# MCP23017_I_v1_0.net
KiCad netlist of a schematic drawn in EAGLE
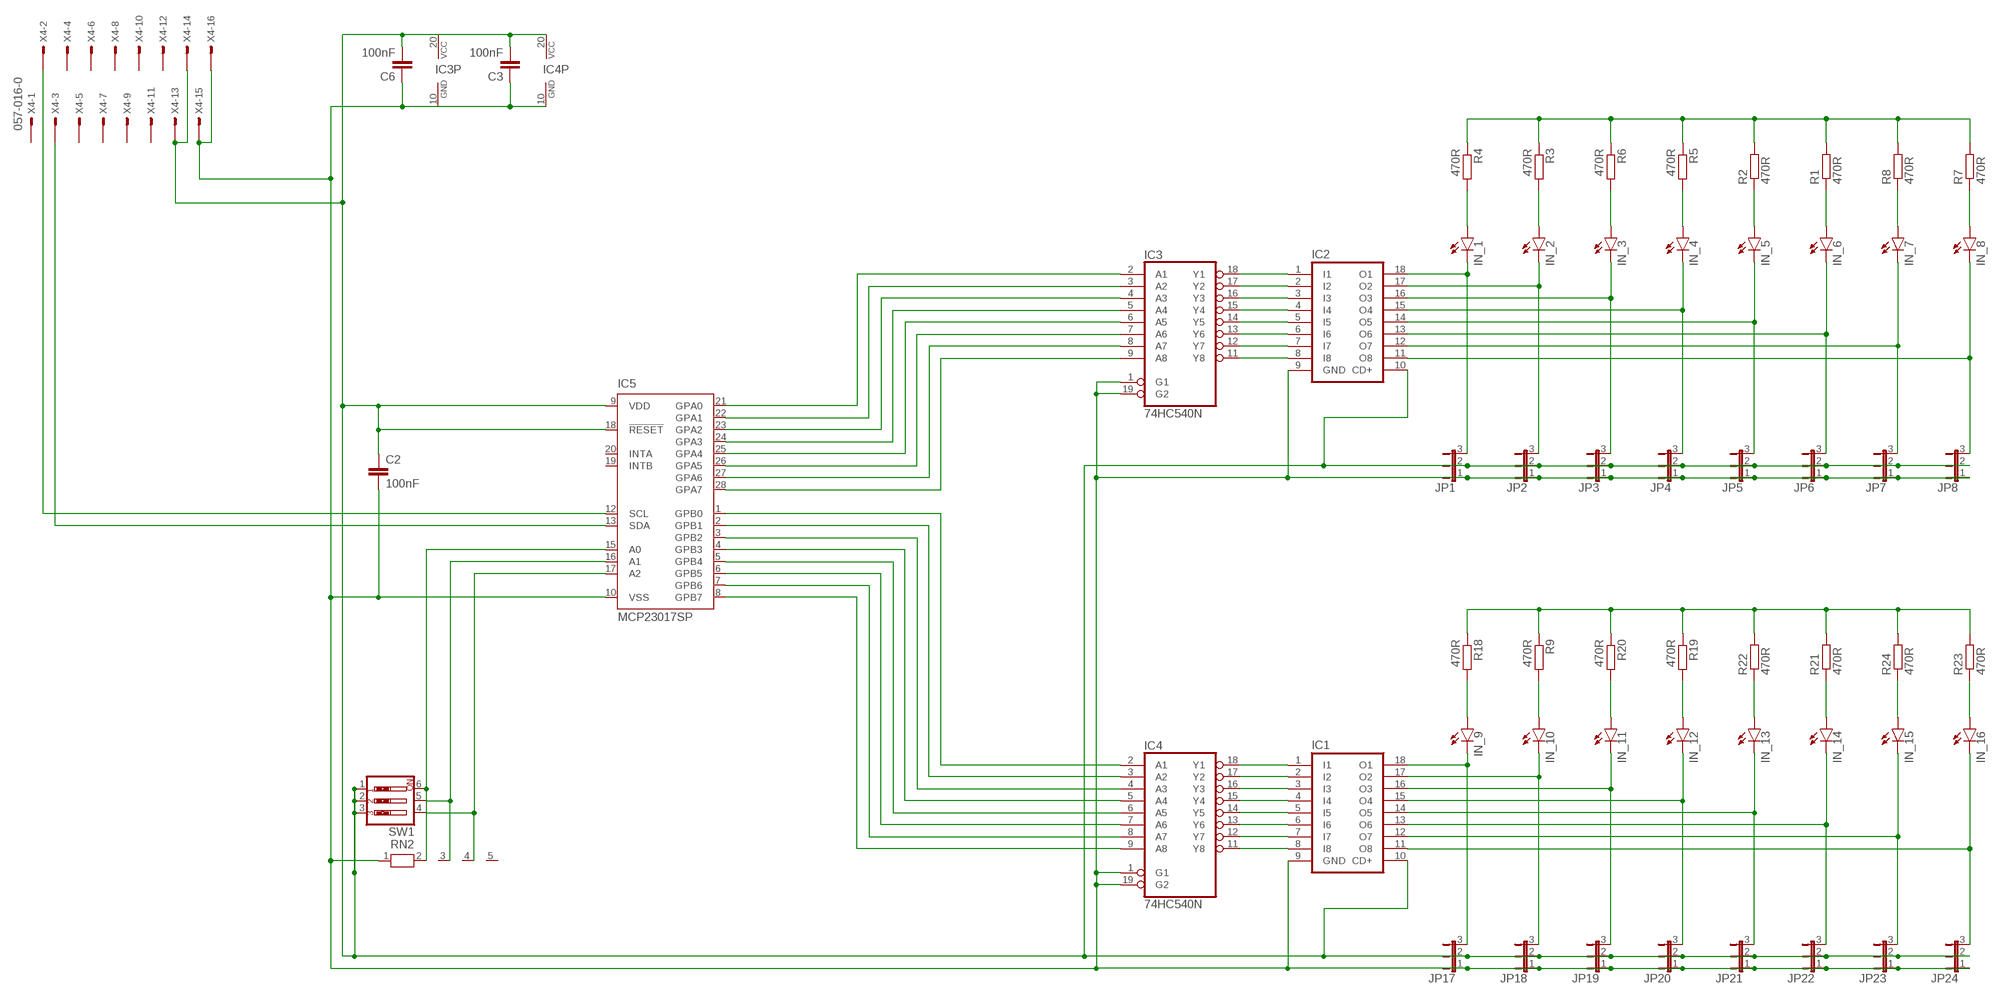
[diagram p0: schematic, sheet 1]

(export (version "E")
  (design (tool "Eeschema 10.0.6"))
  (components
    (comp (ref "C2")
      (value "100nF")
      (footprint "eagle-import:C025-024X044")
      (libsource (lib "eagle-import") (part "C-EU025-024X044"))
    )
    (comp (ref "C3")
      (value "100nF")
      (footprint "eagle-import:C025-024X044")
      (libsource (lib "eagle-import") (part "C-EU025-024X044"))
    )
    (comp (ref "C6")
      (value "100nF")
      (footprint "eagle-import:C025-024X044")
      (libsource (lib "eagle-import") (part "C-EU025-024X044"))
    )
    (comp (ref "IC1")
      (value "ULN2803A")
      (footprint "eagle-import:DIL18")
      (libsource (lib "eagle-import") (part "ULN2803A"))
    )
    (comp (ref "IC2")
      (value "ULN2803A")
      (footprint "eagle-import:DIL18")
      (libsource (lib "eagle-import") (part "ULN2803A"))
    )
    (comp (ref "IC3")
      (value "74HC540N")
      (footprint "eagle-import:DIL20")
      (libsource (lib "eagle-import") (part "74540NHC"))
    )
    (comp (ref "IC4")
      (value "74HC540N")
      (footprint "eagle-import:DIL20")
      (libsource (lib "eagle-import") (part "74540NHC"))
    )
    (comp (ref "IC5")
      (value "MCP23017SP")
      (footprint "eagle-import:DIL28-3")
      (libsource (lib "eagle-import") (part "MCP23017SP"))
    )
    (comp (ref "IN_1")
      (value "LED3MM")
      (footprint "eagle-import:LED3MM")
      (libsource (lib "eagle-import") (part "LED3MM"))
    )
    (comp (ref "IN_2")
      (value "LED3MM")
      (footprint "eagle-import:LED3MM")
      (libsource (lib "eagle-import") (part "LED3MM"))
    )
    (comp (ref "IN_3")
      (value "LED3MM")
      (footprint "eagle-import:LED3MM")
      (libsource (lib "eagle-import") (part "LED3MM"))
    )
    (comp (ref "IN_4")
      (value "LED3MM")
      (footprint "eagle-import:LED3MM")
      (libsource (lib "eagle-import") (part "LED3MM"))
    )
    (comp (ref "IN_5")
      (value "LED3MM")
      (footprint "eagle-import:LED3MM")
      (libsource (lib "eagle-import") (part "LED3MM"))
    )
    (comp (ref "IN_6")
      (value "LED3MM")
      (footprint "eagle-import:LED3MM")
      (libsource (lib "eagle-import") (part "LED3MM"))
    )
    (comp (ref "IN_7")
      (value "LED3MM")
      (footprint "eagle-import:LED3MM")
      (libsource (lib "eagle-import") (part "LED3MM"))
    )
    (comp (ref "IN_8")
      (value "LED3MM")
      (footprint "eagle-import:LED3MM")
      (libsource (lib "eagle-import") (part "LED3MM"))
    )
    (comp (ref "IN_9")
      (value "LED3MM")
      (footprint "eagle-import:LED3MM")
      (libsource (lib "eagle-import") (part "LED3MM"))
    )
    (comp (ref "IN_10")
      (value "LED3MM")
      (footprint "eagle-import:LED3MM")
      (libsource (lib "eagle-import") (part "LED3MM"))
    )
    (comp (ref "IN_11")
      (value "LED3MM")
      (footprint "eagle-import:LED3MM")
      (libsource (lib "eagle-import") (part "LED3MM"))
    )
    (comp (ref "IN_12")
      (value "LED3MM")
      (footprint "eagle-import:LED3MM")
      (libsource (lib "eagle-import") (part "LED3MM"))
    )
    (comp (ref "IN_13")
      (value "LED3MM")
      (footprint "eagle-import:LED3MM")
      (libsource (lib "eagle-import") (part "LED3MM"))
    )
    (comp (ref "IN_14")
      (value "LED3MM")
      (footprint "eagle-import:LED3MM")
      (libsource (lib "eagle-import") (part "LED3MM"))
    )
    (comp (ref "IN_15")
      (value "LED3MM")
      (footprint "eagle-import:LED3MM")
      (libsource (lib "eagle-import") (part "LED3MM"))
    )
    (comp (ref "IN_16")
      (value "LED3MM")
      (footprint "eagle-import:LED3MM")
      (libsource (lib "eagle-import") (part "LED3MM"))
    )
    (comp (ref "JP1")
      (value "JP2E")
      (footprint "eagle-import:JP2")
      (libsource (lib "eagle-import") (part "JP2E"))
    )
    (comp (ref "JP2")
      (value "JP2E")
      (footprint "eagle-import:JP2")
      (libsource (lib "eagle-import") (part "JP2E"))
    )
    (comp (ref "JP3")
      (value "JP2E")
      (footprint "eagle-import:JP2")
      (libsource (lib "eagle-import") (part "JP2E"))
    )
    (comp (ref "JP4")
      (value "JP2E")
      (footprint "eagle-import:JP2")
      (libsource (lib "eagle-import") (part "JP2E"))
    )
    (comp (ref "JP5")
      (value "JP2E")
      (footprint "eagle-import:JP2")
      (libsource (lib "eagle-import") (part "JP2E"))
    )
    (comp (ref "JP6")
      (value "JP2E")
      (footprint "eagle-import:JP2")
      (libsource (lib "eagle-import") (part "JP2E"))
    )
    (comp (ref "JP7")
      (value "JP2E")
      (footprint "eagle-import:JP2")
      (libsource (lib "eagle-import") (part "JP2E"))
    )
    (comp (ref "JP8")
      (value "JP2E")
      (footprint "eagle-import:JP2")
      (libsource (lib "eagle-import") (part "JP2E"))
    )
    (comp (ref "JP17")
      (value "JP2E")
      (footprint "eagle-import:JP2")
      (libsource (lib "eagle-import") (part "JP2E"))
    )
    (comp (ref "JP18")
      (value "JP2E")
      (footprint "eagle-import:JP2")
      (libsource (lib "eagle-import") (part "JP2E"))
    )
    (comp (ref "JP19")
      (value "JP2E")
      (footprint "eagle-import:JP2")
      (libsource (lib "eagle-import") (part "JP2E"))
    )
    (comp (ref "JP20")
      (value "JP2E")
      (footprint "eagle-import:JP2")
      (libsource (lib "eagle-import") (part "JP2E"))
    )
    (comp (ref "JP21")
      (value "JP2E")
      (footprint "eagle-import:JP2")
      (libsource (lib "eagle-import") (part "JP2E"))
    )
    (comp (ref "JP22")
      (value "JP2E")
      (footprint "eagle-import:JP2")
      (libsource (lib "eagle-import") (part "JP2E"))
    )
    (comp (ref "JP23")
      (value "JP2E")
      (footprint "eagle-import:JP2")
      (libsource (lib "eagle-import") (part "JP2E"))
    )
    (comp (ref "JP24")
      (value "JP2E")
      (footprint "eagle-import:JP2")
      (libsource (lib "eagle-import") (part "JP2E"))
    )
    (comp (ref "R1")
      (value "470R")
      (footprint "eagle-import:0309_10")
      (libsource (lib "eagle-import") (part "R-EU_0309/10"))
    )
    (comp (ref "R2")
      (value "470R")
      (footprint "eagle-import:0309_10")
      (libsource (lib "eagle-import") (part "R-EU_0309/10"))
    )
    (comp (ref "R3")
      (value "470R")
      (footprint "eagle-import:0309_10")
      (libsource (lib "eagle-import") (part "R-EU_0309/10"))
    )
    (comp (ref "R4")
      (value "470R")
      (footprint "eagle-import:0309_10")
      (libsource (lib "eagle-import") (part "R-EU_0309/10"))
    )
    (comp (ref "R5")
      (value "470R")
      (footprint "eagle-import:0309_10")
      (libsource (lib "eagle-import") (part "R-EU_0309/10"))
    )
    (comp (ref "R6")
      (value "470R")
      (footprint "eagle-import:0309_10")
      (libsource (lib "eagle-import") (part "R-EU_0309/10"))
    )
    (comp (ref "R7")
      (value "470R")
      (footprint "eagle-import:0309_10")
      (libsource (lib "eagle-import") (part "R-EU_0309/10"))
    )
    (comp (ref "R8")
      (value "470R")
      (footprint "eagle-import:0309_10")
      (libsource (lib "eagle-import") (part "R-EU_0309/10"))
    )
    (comp (ref "R9")
      (value "470R")
      (footprint "eagle-import:0309_10")
      (libsource (lib "eagle-import") (part "R-EU_0309/10"))
    )
    (comp (ref "R18")
      (value "470R")
      (footprint "eagle-import:0309_10")
      (libsource (lib "eagle-import") (part "R-EU_0309/10"))
    )
    (comp (ref "R19")
      (value "470R")
      (footprint "eagle-import:0309_10")
      (libsource (lib "eagle-import") (part "R-EU_0309/10"))
    )
    (comp (ref "R20")
      (value "470R")
      (footprint "eagle-import:0309_10")
      (libsource (lib "eagle-import") (part "R-EU_0309/10"))
    )
    (comp (ref "R21")
      (value "470R")
      (footprint "eagle-import:0309_10")
      (libsource (lib "eagle-import") (part "R-EU_0309/10"))
    )
    (comp (ref "R22")
      (value "470R")
      (footprint "eagle-import:0309_10")
      (libsource (lib "eagle-import") (part "R-EU_0309/10"))
    )
    (comp (ref "R23")
      (value "470R")
      (footprint "eagle-import:0309_10")
      (libsource (lib "eagle-import") (part "R-EU_0309/10"))
    )
    (comp (ref "R24")
      (value "470R")
      (footprint "eagle-import:0309_10")
      (libsource (lib "eagle-import") (part "R-EU_0309/10"))
    )
    (comp (ref "RN2")
      (value "RN04")
      (footprint "eagle-import:RN-5")
      (libsource (lib "eagle-import") (part "RN04"))
    )
    (comp (ref "SW1")
      (value "SW_DIP-3")
      (footprint "eagle-import:EDG-03")
      (libsource (lib "eagle-import") (part "SW_DIP-3"))
    )
    (comp (ref "X4")
      (value "057-016-0")
      (footprint "eagle-import:057-016-0")
      (libsource (lib "eagle-import") (part "057-016-0"))
    )
  )
  (nets
    (net (code "1") (name "/VCC5.2") (class "Default")
      (node (ref "C2") (pin "1") (pinfunction "1_1") (pintype "passive"))
      (node (ref "C3") (pin "2") (pinfunction "2_2") (pintype "passive"))
      (node (ref "C6") (pin "2") (pinfunction "2_2") (pintype "passive"))
      (node (ref "IC1") (pin "10") (pinfunction "CD+_10") (pintype "passive"))
      (node (ref "IC2") (pin "10") (pinfunction "CD+_10") (pintype "passive"))
      (node (ref "IC3") (pin "20") (pinfunction "VCC_20") (pintype "power_in"))
      (node (ref "IC4") (pin "20") (pinfunction "VCC_20") (pintype "power_in"))
      (node (ref "IC5") (pin "18") (pinfunction "~{RESET}_18") (pintype "input"))
      (node (ref "IC5") (pin "9") (pinfunction "VDD_9") (pintype "power_in"))
      (node (ref "JP1") (pin "2") (pinfunction "2_2") (pintype "passive"))
      (node (ref "JP17") (pin "2") (pinfunction "2_2") (pintype "passive"))
      (node (ref "JP18") (pin "2") (pinfunction "2_2") (pintype "passive"))
      (node (ref "JP19") (pin "2") (pinfunction "2_2") (pintype "passive"))
      (node (ref "JP2") (pin "2") (pinfunction "2_2") (pintype "passive"))
      (node (ref "JP20") (pin "2") (pinfunction "2_2") (pintype "passive"))
      (node (ref "JP21") (pin "2") (pinfunction "2_2") (pintype "passive"))
      (node (ref "JP22") (pin "2") (pinfunction "2_2") (pintype "passive"))
      (node (ref "JP23") (pin "2") (pinfunction "2_2") (pintype "passive"))
      (node (ref "JP24") (pin "2") (pinfunction "2_2") (pintype "passive"))
      (node (ref "JP3") (pin "2") (pinfunction "2_2") (pintype "passive"))
      (node (ref "JP4") (pin "2") (pinfunction "2_2") (pintype "passive"))
      (node (ref "JP5") (pin "2") (pinfunction "2_2") (pintype "passive"))
      (node (ref "JP6") (pin "2") (pinfunction "2_2") (pintype "passive"))
      (node (ref "JP7") (pin "2") (pinfunction "2_2") (pintype "passive"))
      (node (ref "JP8") (pin "2") (pinfunction "2_2") (pintype "passive"))
      (node (ref "R1") (pin "2") (pinfunction "2_2") (pintype "passive"))
      (node (ref "R18") (pin "1") (pinfunction "1_1") (pintype "passive"))
      (node (ref "R19") (pin "1") (pinfunction "1_1") (pintype "passive"))
      (node (ref "R2") (pin "2") (pinfunction "2_2") (pintype "passive"))
      (node (ref "R20") (pin "1") (pinfunction "1_1") (pintype "passive"))
      (node (ref "R21") (pin "2") (pinfunction "2_2") (pintype "passive"))
      (node (ref "R22") (pin "2") (pinfunction "2_2") (pintype "passive"))
      (node (ref "R23") (pin "2") (pinfunction "2_2") (pintype "passive"))
      (node (ref "R24") (pin "2") (pinfunction "2_2") (pintype "passive"))
      (node (ref "R3") (pin "1") (pinfunction "1_1") (pintype "passive"))
      (node (ref "R4") (pin "1") (pinfunction "1_1") (pintype "passive"))
      (node (ref "R5") (pin "1") (pinfunction "1_1") (pintype "passive"))
      (node (ref "R6") (pin "1") (pinfunction "1_1") (pintype "passive"))
      (node (ref "R7") (pin "2") (pinfunction "2_2") (pintype "passive"))
      (node (ref "R8") (pin "2") (pinfunction "2_2") (pintype "passive"))
      (node (ref "R9") (pin "1") (pinfunction "1_1") (pintype "passive"))
      (node (ref "SW1") (pin "1") (pinfunction "1_1") (pintype "passive"))
      (node (ref "SW1") (pin "2") (pinfunction "2_2") (pintype "passive"))
      (node (ref "SW1") (pin "3") (pinfunction "3_3") (pintype "passive"))
      (node (ref "X4") (pin "13") (pinfunction "S_13") (pintype "passive"))
      (node (ref "X4") (pin "14") (pinfunction "S_14") (pintype "passive"))
    )
    (net (code "2") (name "Net-(IC1-GND)") (class "Default")
      (node (ref "C2") (pin "2") (pinfunction "2_2") (pintype "passive"))
      (node (ref "C3") (pin "1") (pinfunction "1_1") (pintype "passive"))
      (node (ref "C6") (pin "1") (pinfunction "1_1") (pintype "passive"))
      (node (ref "IC1") (pin "9") (pinfunction "GND_9") (pintype "power_in"))
      (node (ref "IC2") (pin "9") (pinfunction "GND_9") (pintype "power_in"))
      (node (ref "IC3") (pin "1") (pinfunction "G1_1") (pintype "input"))
      (node (ref "IC3") (pin "10") (pinfunction "GND_10") (pintype "power_in"))
      (node (ref "IC3") (pin "19") (pinfunction "G2_19") (pintype "input"))
      (node (ref "IC4") (pin "1") (pinfunction "G1_1") (pintype "input"))
      (node (ref "IC4") (pin "10") (pinfunction "GND_10") (pintype "power_in"))
      (node (ref "IC4") (pin "19") (pinfunction "G2_19") (pintype "input"))
      (node (ref "IC5") (pin "10") (pinfunction "VSS_10") (pintype "power_in"))
      (node (ref "JP1") (pin "1") (pinfunction "1_1") (pintype "passive"))
      (node (ref "JP17") (pin "1") (pinfunction "1_1") (pintype "passive"))
      (node (ref "JP18") (pin "1") (pinfunction "1_1") (pintype "passive"))
      (node (ref "JP19") (pin "1") (pinfunction "1_1") (pintype "passive"))
      (node (ref "JP2") (pin "1") (pinfunction "1_1") (pintype "passive"))
      (node (ref "JP20") (pin "1") (pinfunction "1_1") (pintype "passive"))
      (node (ref "JP21") (pin "1") (pinfunction "1_1") (pintype "passive"))
      (node (ref "JP22") (pin "1") (pinfunction "1_1") (pintype "passive"))
      (node (ref "JP23") (pin "1") (pinfunction "1_1") (pintype "passive"))
      (node (ref "JP24") (pin "1") (pinfunction "1_1") (pintype "passive"))
      (node (ref "JP3") (pin "1") (pinfunction "1_1") (pintype "passive"))
      (node (ref "JP4") (pin "1") (pinfunction "1_1") (pintype "passive"))
      (node (ref "JP5") (pin "1") (pinfunction "1_1") (pintype "passive"))
      (node (ref "JP6") (pin "1") (pinfunction "1_1") (pintype "passive"))
      (node (ref "JP7") (pin "1") (pinfunction "1_1") (pintype "passive"))
      (node (ref "JP8") (pin "1") (pinfunction "1_1") (pintype "passive"))
      (node (ref "RN2") (pin "1") (pinfunction "1_1") (pintype "passive"))
      (node (ref "X4") (pin "15") (pinfunction "S_15") (pintype "passive"))
      (node (ref "X4") (pin "16") (pinfunction "S_16") (pintype "passive"))
    )
    (net (code "3") (name "Net-(IC1-I1)") (class "Default")
      (node (ref "IC1") (pin "1") (pinfunction "I1_1") (pintype "input"))
      (node (ref "IC4") (pin "18") (pinfunction "Y1_18") (pintype "tri_state"))
    )
    (net (code "4") (name "Net-(IC1-I2)") (class "Default")
      (node (ref "IC1") (pin "2") (pinfunction "I2_2") (pintype "input"))
      (node (ref "IC4") (pin "17") (pinfunction "Y2_17") (pintype "tri_state"))
    )
    (net (code "5") (name "Net-(IC1-I3)") (class "Default")
      (node (ref "IC1") (pin "3") (pinfunction "I3_3") (pintype "input"))
      (node (ref "IC4") (pin "16") (pinfunction "Y3_16") (pintype "tri_state"))
    )
    (net (code "6") (name "Net-(IC1-I4)") (class "Default")
      (node (ref "IC1") (pin "4") (pinfunction "I4_4") (pintype "input"))
      (node (ref "IC4") (pin "15") (pinfunction "Y4_15") (pintype "tri_state"))
    )
    (net (code "7") (name "Net-(IC1-I5)") (class "Default")
      (node (ref "IC1") (pin "5") (pinfunction "I5_5") (pintype "input"))
      (node (ref "IC4") (pin "14") (pinfunction "Y5_14") (pintype "tri_state"))
    )
    (net (code "8") (name "Net-(IC1-I6)") (class "Default")
      (node (ref "IC1") (pin "6") (pinfunction "I6_6") (pintype "input"))
      (node (ref "IC4") (pin "13") (pinfunction "Y6_13") (pintype "tri_state"))
    )
    (net (code "9") (name "Net-(IC1-I7)") (class "Default")
      (node (ref "IC1") (pin "7") (pinfunction "I7_7") (pintype "input"))
      (node (ref "IC4") (pin "12") (pinfunction "Y7_12") (pintype "tri_state"))
    )
    (net (code "10") (name "Net-(IC1-I8)") (class "Default")
      (node (ref "IC1") (pin "8") (pinfunction "I8_8") (pintype "input"))
      (node (ref "IC4") (pin "11") (pinfunction "Y8_11") (pintype "tri_state"))
    )
    (net (code "11") (name "Net-(IC1-O1)") (class "Default")
      (node (ref "IC1") (pin "18") (pinfunction "O1_18") (pintype "open_collector"))
      (node (ref "IN_9") (pin "K") (pinfunction "C_K") (pintype "passive"))
      (node (ref "JP17") (pin "3") (pinfunction "3_3") (pintype "passive"))
    )
    (net (code "12") (name "Net-(IC1-O2)") (class "Default")
      (node (ref "IC1") (pin "17") (pinfunction "O2_17") (pintype "open_collector"))
      (node (ref "IN_10") (pin "K") (pinfunction "C_K") (pintype "passive"))
      (node (ref "JP18") (pin "3") (pinfunction "3_3") (pintype "passive"))
    )
    (net (code "13") (name "Net-(IC1-O3)") (class "Default")
      (node (ref "IC1") (pin "16") (pinfunction "O3_16") (pintype "open_collector"))
      (node (ref "IN_11") (pin "K") (pinfunction "C_K") (pintype "passive"))
      (node (ref "JP19") (pin "3") (pinfunction "3_3") (pintype "passive"))
    )
    (net (code "14") (name "Net-(IC1-O4)") (class "Default")
      (node (ref "IC1") (pin "15") (pinfunction "O4_15") (pintype "open_collector"))
      (node (ref "IN_12") (pin "K") (pinfunction "C_K") (pintype "passive"))
      (node (ref "JP20") (pin "3") (pinfunction "3_3") (pintype "passive"))
    )
    (net (code "15") (name "Net-(IC1-O5)") (class "Default")
      (node (ref "IC1") (pin "14") (pinfunction "O5_14") (pintype "open_collector"))
      (node (ref "IN_13") (pin "K") (pinfunction "C_K") (pintype "passive"))
      (node (ref "JP21") (pin "3") (pinfunction "3_3") (pintype "passive"))
    )
    (net (code "16") (name "Net-(IC1-O6)") (class "Default")
      (node (ref "IC1") (pin "13") (pinfunction "O6_13") (pintype "open_collector"))
      (node (ref "IN_14") (pin "K") (pinfunction "C_K") (pintype "passive"))
      (node (ref "JP22") (pin "3") (pinfunction "3_3") (pintype "passive"))
    )
    (net (code "17") (name "Net-(IC1-O7)") (class "Default")
      (node (ref "IC1") (pin "12") (pinfunction "O7_12") (pintype "open_collector"))
      (node (ref "IN_15") (pin "K") (pinfunction "C_K") (pintype "passive"))
      (node (ref "JP23") (pin "3") (pinfunction "3_3") (pintype "passive"))
    )
    (net (code "18") (name "Net-(IC1-O8)") (class "Default")
      (node (ref "IC1") (pin "11") (pinfunction "O8_11") (pintype "open_collector"))
      (node (ref "IN_16") (pin "K") (pinfunction "C_K") (pintype "passive"))
      (node (ref "JP24") (pin "3") (pinfunction "3_3") (pintype "passive"))
    )
    (net (code "19") (name "Net-(IC2-I1)") (class "Default")
      (node (ref "IC2") (pin "1") (pinfunction "I1_1") (pintype "input"))
      (node (ref "IC3") (pin "18") (pinfunction "Y1_18") (pintype "tri_state"))
    )
    (net (code "20") (name "Net-(IC2-I2)") (class "Default")
      (node (ref "IC2") (pin "2") (pinfunction "I2_2") (pintype "input"))
      (node (ref "IC3") (pin "17") (pinfunction "Y2_17") (pintype "tri_state"))
    )
    (net (code "21") (name "Net-(IC2-I3)") (class "Default")
      (node (ref "IC2") (pin "3") (pinfunction "I3_3") (pintype "input"))
      (node (ref "IC3") (pin "16") (pinfunction "Y3_16") (pintype "tri_state"))
    )
    (net (code "22") (name "Net-(IC2-I4)") (class "Default")
      (node (ref "IC2") (pin "4") (pinfunction "I4_4") (pintype "input"))
      (node (ref "IC3") (pin "15") (pinfunction "Y4_15") (pintype "tri_state"))
    )
    (net (code "23") (name "Net-(IC2-I5)") (class "Default")
      (node (ref "IC2") (pin "5") (pinfunction "I5_5") (pintype "input"))
      (node (ref "IC3") (pin "14") (pinfunction "Y5_14") (pintype "tri_state"))
    )
    (net (code "24") (name "Net-(IC2-I6)") (class "Default")
      (node (ref "IC2") (pin "6") (pinfunction "I6_6") (pintype "input"))
      (node (ref "IC3") (pin "13") (pinfunction "Y6_13") (pintype "tri_state"))
    )
    (net (code "25") (name "Net-(IC2-I7)") (class "Default")
      (node (ref "IC2") (pin "7") (pinfunction "I7_7") (pintype "input"))
      (node (ref "IC3") (pin "12") (pinfunction "Y7_12") (pintype "tri_state"))
    )
    (net (code "26") (name "Net-(IC2-I8)") (class "Default")
      (node (ref "IC2") (pin "8") (pinfunction "I8_8") (pintype "input"))
      (node (ref "IC3") (pin "11") (pinfunction "Y8_11") (pintype "tri_state"))
    )
    (net (code "27") (name "Net-(IC2-O1)") (class "Default")
      (node (ref "IC2") (pin "18") (pinfunction "O1_18") (pintype "open_collector"))
      (node (ref "IN_1") (pin "K") (pinfunction "C_K") (pintype "passive"))
      (node (ref "JP1") (pin "3") (pinfunction "3_3") (pintype "passive"))
    )
    (net (code "28") (name "Net-(IC2-O2)") (class "Default")
      (node (ref "IC2") (pin "17") (pinfunction "O2_17") (pintype "open_collector"))
      (node (ref "IN_2") (pin "K") (pinfunction "C_K") (pintype "passive"))
      (node (ref "JP2") (pin "3") (pinfunction "3_3") (pintype "passive"))
    )
    (net (code "29") (name "Net-(IC2-O3)") (class "Default")
      (node (ref "IC2") (pin "16") (pinfunction "O3_16") (pintype "open_collector"))
      (node (ref "IN_3") (pin "K") (pinfunction "C_K") (pintype "passive"))
      (node (ref "JP3") (pin "3") (pinfunction "3_3") (pintype "passive"))
    )
    (net (code "30") (name "Net-(IC2-O4)") (class "Default")
      (node (ref "IC2") (pin "15") (pinfunction "O4_15") (pintype "open_collector"))
      (node (ref "IN_4") (pin "K") (pinfunction "C_K") (pintype "passive"))
      (node (ref "JP4") (pin "3") (pinfunction "3_3") (pintype "passive"))
    )
    (net (code "31") (name "Net-(IC2-O5)") (class "Default")
      (node (ref "IC2") (pin "14") (pinfunction "O5_14") (pintype "open_collector"))
      (node (ref "IN_5") (pin "K") (pinfunction "C_K") (pintype "passive"))
      (node (ref "JP5") (pin "3") (pinfunction "3_3") (pintype "passive"))
    )
    (net (code "32") (name "Net-(IC2-O6)") (class "Default")
      (node (ref "IC2") (pin "13") (pinfunction "O6_13") (pintype "open_collector"))
      (node (ref "IN_6") (pin "K") (pinfunction "C_K") (pintype "passive"))
      (node (ref "JP6") (pin "3") (pinfunction "3_3") (pintype "passive"))
    )
    (net (code "33") (name "Net-(IC2-O7)") (class "Default")
      (node (ref "IC2") (pin "12") (pinfunction "O7_12") (pintype "open_collector"))
      (node (ref "IN_7") (pin "K") (pinfunction "C_K") (pintype "passive"))
      (node (ref "JP7") (pin "3") (pinfunction "3_3") (pintype "passive"))
    )
    (net (code "34") (name "Net-(IC2-O8)") (class "Default")
      (node (ref "IC2") (pin "11") (pinfunction "O8_11") (pintype "open_collector"))
      (node (ref "IN_8") (pin "K") (pinfunction "C_K") (pintype "passive"))
      (node (ref "JP8") (pin "3") (pinfunction "3_3") (pintype "passive"))
    )
    (net (code "35") (name "Net-(IC3A-A1)") (class "Default")
      (node (ref "IC3") (pin "2") (pinfunction "A1_2") (pintype "input"))
      (node (ref "IC5") (pin "21") (pinfunction "GPA0_21") (pintype "bidirectional"))
    )
    (net (code "36") (name "Net-(IC3A-A2)") (class "Default")
      (node (ref "IC3") (pin "3") (pinfunction "A2_3") (pintype "input"))
      (node (ref "IC5") (pin "22") (pinfunction "GPA1_22") (pintype "bidirectional"))
    )
    (net (code "37") (name "Net-(IC3A-A3)") (class "Default")
      (node (ref "IC3") (pin "4") (pinfunction "A3_4") (pintype "input"))
      (node (ref "IC5") (pin "23") (pinfunction "GPA2_23") (pintype "bidirectional"))
    )
    (net (code "38") (name "Net-(IC3A-A4)") (class "Default")
      (node (ref "IC3") (pin "5") (pinfunction "A4_5") (pintype "input"))
      (node (ref "IC5") (pin "24") (pinfunction "GPA3_24") (pintype "bidirectional"))
    )
    (net (code "39") (name "Net-(IC3A-A5)") (class "Default")
      (node (ref "IC3") (pin "6") (pinfunction "A5_6") (pintype "input"))
      (node (ref "IC5") (pin "25") (pinfunction "GPA4_25") (pintype "bidirectional"))
    )
    (net (code "40") (name "Net-(IC3A-A6)") (class "Default")
      (node (ref "IC3") (pin "7") (pinfunction "A6_7") (pintype "input"))
      (node (ref "IC5") (pin "26") (pinfunction "GPA5_26") (pintype "bidirectional"))
    )
    (net (code "41") (name "Net-(IC3A-A7)") (class "Default")
      (node (ref "IC3") (pin "8") (pinfunction "A7_8") (pintype "input"))
      (node (ref "IC5") (pin "27") (pinfunction "GPA6_27") (pintype "bidirectional"))
    )
    (net (code "42") (name "Net-(IC3A-A8)") (class "Default")
      (node (ref "IC3") (pin "9") (pinfunction "A8_9") (pintype "input"))
      (node (ref "IC5") (pin "28") (pinfunction "GPA7_28") (pintype "bidirectional"))
    )
    (net (code "43") (name "Net-(IC4A-A1)") (class "Default")
      (node (ref "IC4") (pin "2") (pinfunction "A1_2") (pintype "input"))
      (node (ref "IC5") (pin "1") (pinfunction "GPB0_1") (pintype "bidirectional"))
    )
    (net (code "44") (name "Net-(IC4A-A2)") (class "Default")
      (node (ref "IC4") (pin "3") (pinfunction "A2_3") (pintype "input"))
      (node (ref "IC5") (pin "2") (pinfunction "GPB1_2") (pintype "bidirectional"))
    )
    (net (code "45") (name "Net-(IC4A-A3)") (class "Default")
      (node (ref "IC4") (pin "4") (pinfunction "A3_4") (pintype "input"))
      (node (ref "IC5") (pin "3") (pinfunction "GPB2_3") (pintype "bidirectional"))
    )
    (net (code "46") (name "Net-(IC4A-A4)") (class "Default")
      (node (ref "IC4") (pin "5") (pinfunction "A4_5") (pintype "input"))
      (node (ref "IC5") (pin "4") (pinfunction "GPB3_4") (pintype "bidirectional"))
    )
    (net (code "47") (name "Net-(IC4A-A5)") (class "Default")
      (node (ref "IC4") (pin "6") (pinfunction "A5_6") (pintype "input"))
      (node (ref "IC5") (pin "5") (pinfunction "GPB4_5") (pintype "bidirectional"))
    )
    (net (code "48") (name "Net-(IC4A-A6)") (class "Default")
      (node (ref "IC4") (pin "7") (pinfunction "A6_7") (pintype "input"))
      (node (ref "IC5") (pin "6") (pinfunction "GPB5_6") (pintype "bidirectional"))
    )
    (net (code "49") (name "Net-(IC4A-A7)") (class "Default")
      (node (ref "IC4") (pin "8") (pinfunction "A7_8") (pintype "input"))
      (node (ref "IC5") (pin "7") (pinfunction "GPB6_7") (pintype "bidirectional"))
    )
    (net (code "50") (name "Net-(IC4A-A8)") (class "Default")
      (node (ref "IC4") (pin "9") (pinfunction "A8_9") (pintype "input"))
      (node (ref "IC5") (pin "8") (pinfunction "GPB7_8") (pintype "bidirectional"))
    )
    (net (code "51") (name "Net-(IC5-A0)") (class "Default")
      (node (ref "IC5") (pin "15") (pinfunction "A0_15") (pintype "input"))
      (node (ref "RN2") (pin "2") (pinfunction "2_2") (pintype "passive"))
      (node (ref "SW1") (pin "6") (pinfunction "6_6") (pintype "passive"))
    )
    (net (code "52") (name "Net-(IC5-A1)") (class "Default")
      (node (ref "IC5") (pin "16") (pinfunction "A1_16") (pintype "input"))
      (node (ref "RN2") (pin "3") (pinfunction "3_3") (pintype "passive"))
      (node (ref "SW1") (pin "5") (pinfunction "5_5") (pintype "passive"))
    )
    (net (code "53") (name "Net-(IC5-A2)") (class "Default")
      (node (ref "IC5") (pin "17") (pinfunction "A2_17") (pintype "input"))
      (node (ref "RN2") (pin "4") (pinfunction "4_4") (pintype "passive"))
      (node (ref "SW1") (pin "4") (pinfunction "4_4") (pintype "passive"))
    )
    (net (code "54") (name "Net-(IC5-SCL)") (class "Default")
      (node (ref "IC5") (pin "12") (pinfunction "SCL_12") (pintype "input"))
      (node (ref "X4") (pin "2") (pinfunction "S_2") (pintype "passive"))
    )
    (net (code "55") (name "Net-(IC5-SDA)") (class "Default")
      (node (ref "IC5") (pin "13") (pinfunction "SDA_13") (pintype "bidirectional"))
      (node (ref "X4") (pin "3") (pinfunction "S_3") (pintype "passive"))
    )
    (net (code "56") (name "Net-(IN_1-PadA)") (class "Default")
      (node (ref "IN_1") (pin "A") (pinfunction "A_A") (pintype "passive"))
      (node (ref "R4") (pin "2") (pinfunction "2_2") (pintype "passive"))
    )
    (net (code "57") (name "Net-(IN_2-PadA)") (class "Default")
      (node (ref "IN_2") (pin "A") (pinfunction "A_A") (pintype "passive"))
      (node (ref "R3") (pin "2") (pinfunction "2_2") (pintype "passive"))
    )
    (net (code "58") (name "Net-(IN_3-PadA)") (class "Default")
      (node (ref "IN_3") (pin "A") (pinfunction "A_A") (pintype "passive"))
      (node (ref "R6") (pin "2") (pinfunction "2_2") (pintype "passive"))
    )
    (net (code "59") (name "Net-(IN_4-PadA)") (class "Default")
      (node (ref "IN_4") (pin "A") (pinfunction "A_A") (pintype "passive"))
      (node (ref "R5") (pin "2") (pinfunction "2_2") (pintype "passive"))
    )
    (net (code "60") (name "Net-(IN_5-PadA)") (class "Default")
      (node (ref "IN_5") (pin "A") (pinfunction "A_A") (pintype "passive"))
      (node (ref "R2") (pin "1") (pinfunction "1_1") (pintype "passive"))
    )
    (net (code "61") (name "Net-(IN_6-PadA)") (class "Default")
      (node (ref "IN_6") (pin "A") (pinfunction "A_A") (pintype "passive"))
      (node (ref "R1") (pin "1") (pinfunction "1_1") (pintype "passive"))
    )
    (net (code "62") (name "Net-(IN_7-PadA)") (class "Default")
      (node (ref "IN_7") (pin "A") (pinfunction "A_A") (pintype "passive"))
      (node (ref "R8") (pin "1") (pinfunction "1_1") (pintype "passive"))
    )
    (net (code "63") (name "Net-(IN_8-PadA)") (class "Default")
      (node (ref "IN_8") (pin "A") (pinfunction "A_A") (pintype "passive"))
      (node (ref "R7") (pin "1") (pinfunction "1_1") (pintype "passive"))
    )
    (net (code "64") (name "Net-(IN_9-PadA)") (class "Default")
      (node (ref "IN_9") (pin "A") (pinfunction "A_A") (pintype "passive"))
      (node (ref "R18") (pin "2") (pinfunction "2_2") (pintype "passive"))
    )
    (net (code "65") (name "Net-(IN_10-PadA)") (class "Default")
      (node (ref "IN_10") (pin "A") (pinfunction "A_A") (pintype "passive"))
      (node (ref "R9") (pin "2") (pinfunction "2_2") (pintype "passive"))
    )
    (net (code "66") (name "Net-(IN_11-PadA)") (class "Default")
      (node (ref "IN_11") (pin "A") (pinfunction "A_A") (pintype "passive"))
      (node (ref "R20") (pin "2") (pinfunction "2_2") (pintype "passive"))
    )
    (net (code "67") (name "Net-(IN_12-PadA)") (class "Default")
      (node (ref "IN_12") (pin "A") (pinfunction "A_A") (pintype "passive"))
      (node (ref "R19") (pin "2") (pinfunction "2_2") (pintype "passive"))
    )
    (net (code "68") (name "Net-(IN_13-PadA)") (class "Default")
      (node (ref "IN_13") (pin "A") (pinfunction "A_A") (pintype "passive"))
      (node (ref "R22") (pin "1") (pinfunction "1_1") (pintype "passive"))
    )
    (net (code "69") (name "Net-(IN_14-PadA)") (class "Default")
      (node (ref "IN_14") (pin "A") (pinfunction "A_A") (pintype "passive"))
      (node (ref "R21") (pin "1") (pinfunction "1_1") (pintype "passive"))
    )
    (net (code "70") (name "Net-(IN_15-PadA)") (class "Default")
      (node (ref "IN_15") (pin "A") (pinfunction "A_A") (pintype "passive"))
      (node (ref "R24") (pin "1") (pinfunction "1_1") (pintype "passive"))
    )
    (net (code "71") (name "Net-(IN_16-PadA)") (class "Default")
      (node (ref "IN_16") (pin "A") (pinfunction "A_A") (pintype "passive"))
      (node (ref "R23") (pin "1") (pinfunction "1_1") (pintype "passive"))
    )
    (net (code "72") (name "unconnected-(IC5-INTA-Pad20)") (class "Default")
      (node (ref "IC5") (pin "20") (pinfunction "INTA_20") (pintype "output"))
    )
    (net (code "73") (name "unconnected-(IC5-INTB-Pad19)") (class "Default")
      (node (ref "IC5") (pin "19") (pinfunction "INTB_19") (pintype "output"))
    )
    (net (code "74") (name "unconnected-(RN2-Pad5)") (class "Default")
      (node (ref "RN2") (pin "5") (pinfunction "5_5") (pintype "passive"))
    )
    (net (code "75") (name "unconnected-(X4A-S-Pad1)") (class "Default")
      (node (ref "X4") (pin "1") (pinfunction "S_1") (pintype "passive"))
    )
    (net (code "76") (name "unconnected-(X4B-S-Pad10)") (class "Default")
      (node (ref "X4") (pin "10") (pinfunction "S_10") (pintype "passive"))
    )
    (net (code "77") (name "unconnected-(X4C-S-Pad11)") (class "Default")
      (node (ref "X4") (pin "11") (pinfunction "S_11") (pintype "passive"))
    )
    (net (code "78") (name "unconnected-(X4D-S-Pad12)") (class "Default")
      (node (ref "X4") (pin "12") (pinfunction "S_12") (pintype "passive"))
    )
    (net (code "79") (name "unconnected-(X4K-S-Pad4)") (class "Default")
      (node (ref "X4") (pin "4") (pinfunction "S_4") (pintype "passive"))
    )
    (net (code "80") (name "unconnected-(X4L-S-Pad5)") (class "Default")
      (node (ref "X4") (pin "5") (pinfunction "S_5") (pintype "passive"))
    )
    (net (code "81") (name "unconnected-(X4M-S-Pad6)") (class "Default")
      (node (ref "X4") (pin "6") (pinfunction "S_6") (pintype "passive"))
    )
    (net (code "82") (name "unconnected-(X4N-S-Pad7)") (class "Default")
      (node (ref "X4") (pin "7") (pinfunction "S_7") (pintype "passive"))
    )
    (net (code "83") (name "unconnected-(X4O-S-Pad8)") (class "Default")
      (node (ref "X4") (pin "8") (pinfunction "S_8") (pintype "passive"))
    )
    (net (code "84") (name "unconnected-(X4P-S-Pad9)") (class "Default")
      (node (ref "X4") (pin "9") (pinfunction "S_9") (pintype "passive"))
    )
  )
)
